# Signal_Conditioner.net
KiCad netlist of a schematic drawn in Altium Designer
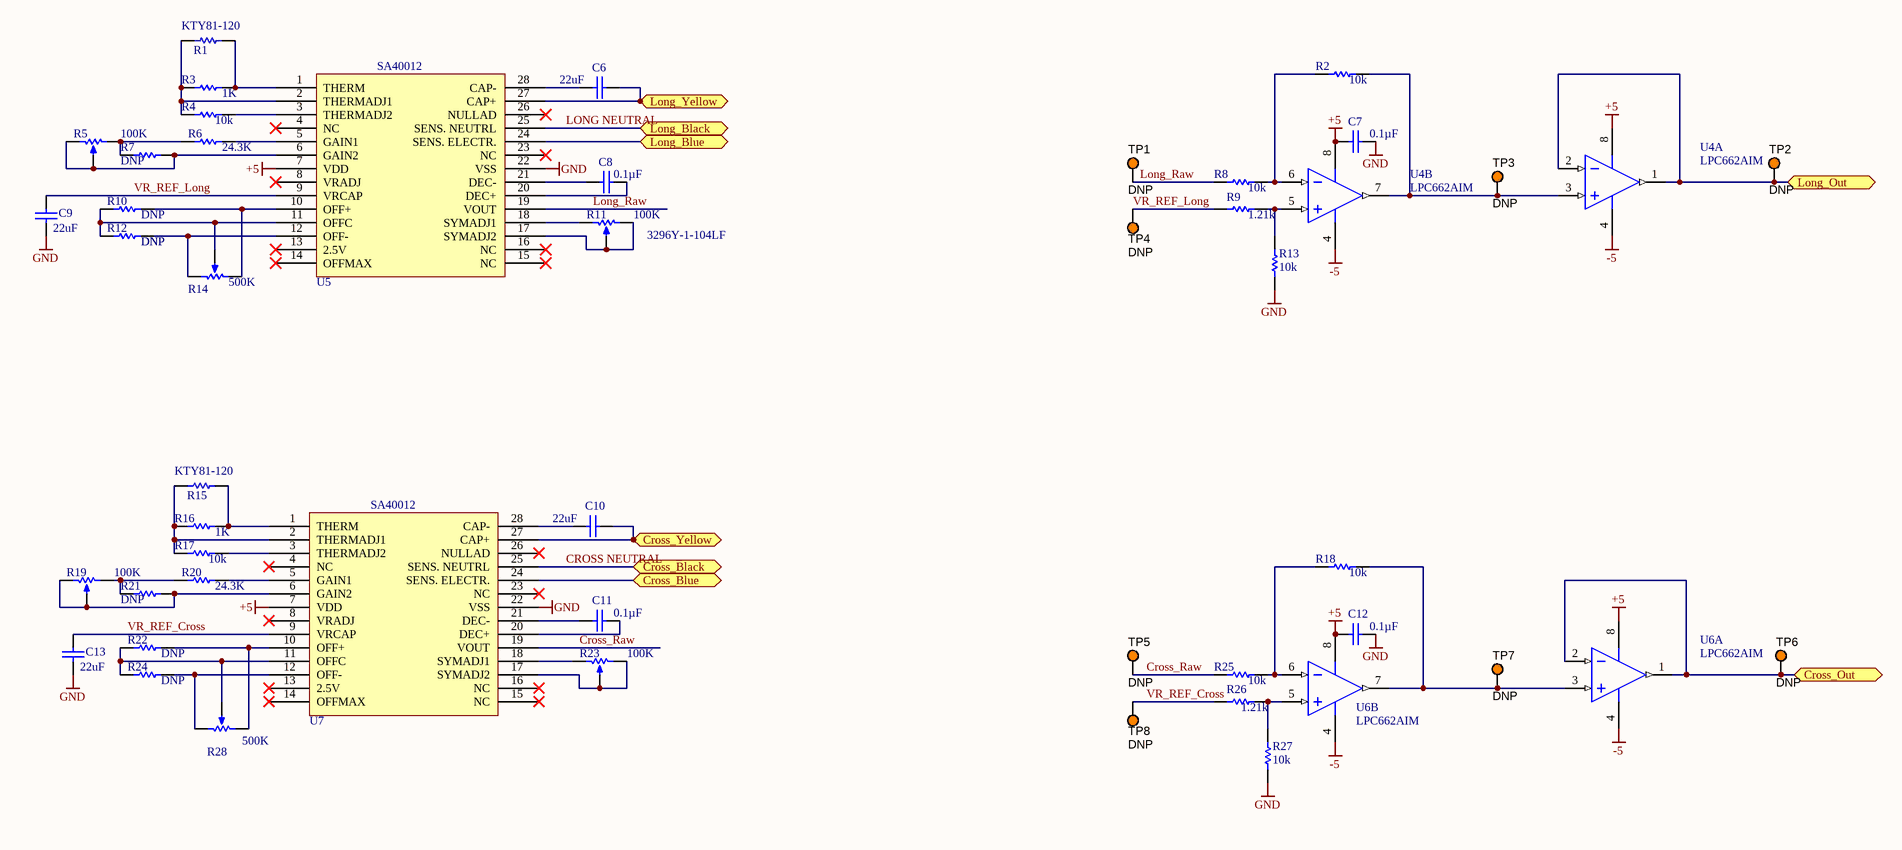
[diagram p0: Signal_Conditioner.SchDoc]

(export (version "E")
  (design (tool "Eeschema 10.0.6"))
  (components
    (comp (ref "C6")
      (value "22uF")
      (footprint "CAPC0805(2012)145_N")
      (description "CAP CER 22UF 16V X5R 0805")
      (fields
        (field (name "MANUFACTURER") "Murata Electronics North America")
        (field (name "MANUFACTURER PART NUMBER") "GRM219R61C226ME15L")
      )
      (libsource (lib "Altium Content Vault") (part "CMP-1036-04795-1"))
    )
    (comp (ref "C7")
      (value "CAP CER 0.1UF 25V X7R 0805")
      (footprint "CAPC0805(2012)145_N")
      (fields
        (field (name "MANUFACTURER") "Murata Electronics North America")
        (field (name "MANUFACTURER PART NUMBER") "GRM21BR71E104KA01L")
        (field (name "CAPACITANCE") "0.1µF")
        (field (name "TOLERANCE") "±10%")
      )
      (libsource (lib "Altium Content Vault") (part "CMP-1036-04795-1"))
    )
    (comp (ref "C8")
      (value "CAP CER 0.1UF 25V X7R 0805")
      (footprint "CAPC0805(2012)145_N")
      (fields
        (field (name "MANUFACTURER") "Murata Electronics North America")
        (field (name "MANUFACTURER PART NUMBER") "GRM21BR71E104KA01L")
        (field (name "CAPACITANCE") "0.1µF")
        (field (name "TOLERANCE") "±10%")
      )
      (libsource (lib "Altium Content Vault") (part "CMP-1036-04795-1"))
    )
    (comp (ref "C9")
      (value "22uF")
      (footprint "CAPC0805(2012)145_N")
      (description "CAP CER 22UF 16V X5R 0805")
      (fields
        (field (name "MANUFACTURER") "Murata Electronics North America")
        (field (name "MANUFACTURER PART NUMBER") "GRM219R61C226ME15L")
      )
      (libsource (lib "Altium Content Vault") (part "CMP-1036-04795-1"))
    )
    (comp (ref "C10")
      (value "22uF")
      (footprint "CAPC0805(2012)145_N")
      (description "CAP CER 22UF 16V X5R 0805")
      (fields
        (field (name "MANUFACTURER") "Murata Electronics North America")
        (field (name "MANUFACTURER PART NUMBER") "GRM219R61C226ME15L")
      )
      (libsource (lib "Altium Content Vault") (part "CMP-1036-04795-1"))
    )
    (comp (ref "C11")
      (value "CAP CER 0.1UF 25V X7R 0805")
      (footprint "CAPC0805(2012)145_N")
      (fields
        (field (name "MANUFACTURER") "Murata Electronics North America")
        (field (name "MANUFACTURER PART NUMBER") "GRM21BR71E104KA01L")
        (field (name "CAPACITANCE") "0.1µF")
        (field (name "TOLERANCE") "±10%")
      )
      (libsource (lib "Altium Content Vault") (part "CMP-1036-04795-1"))
    )
    (comp (ref "C12")
      (value "CAP CER 0.1UF 25V X7R 0805")
      (footprint "CAPC0805(2012)145_N")
      (fields
        (field (name "MANUFACTURER") "Murata Electronics North America")
        (field (name "MANUFACTURER PART NUMBER") "GRM21BR71E104KA01L")
        (field (name "CAPACITANCE") "0.1µF")
        (field (name "TOLERANCE") "±10%")
      )
      (libsource (lib "Altium Content Vault") (part "CMP-1036-04795-1"))
    )
    (comp (ref "C13")
      (value "22uF")
      (footprint "CAPC0805(2012)145_N")
      (description "CAP CER 22UF 16V X5R 0805")
      (fields
        (field (name "MANUFACTURER") "Murata Electronics North America")
        (field (name "MANUFACTURER PART NUMBER") "GRM219R61C226ME15L")
      )
      (libsource (lib "Altium Content Vault") (part "CMP-1036-04795-1"))
    )
    (comp (ref "R1")
      (value "KTY81-120")
      (footprint "KTY81-120")
      (description "THERMISTOR PTC 1K OHM PBCYT2")
      (fields
        (field (name "MANUFACTURER") "NXP USA Inc.")
        (field (name "MANUFACTURER PART NUMBER") "KTY81/120,112")
      )
      (libsource (lib "ZLS_Schematic_lib") (part "KTY81-120"))
    )
    (comp (ref "R2")
      (value "10k")
      (footprint "RESC0805(2012)_L")
      (description "RES SMD 10K OHM 1% 1/8W 0805")
      (fields
        (field (name "MANUFACTURER") "Vishay Dale")
        (field (name "MANUFACTURER PART NUMBER") "CRCW080510K0FKEA")
      )
      (libsource (lib "Altium Content Vault") (part "CMP-1013-00393-1"))
    )
    (comp (ref "R3")
      (value "1K")
      (footprint "RESC0805(2012)_L")
      (description "RES SMD 1K OHM 1% 1/8W 0805")
      (fields
        (field (name "MANUFACTURER") "Vishay Dale")
        (field (name "MANUFACTURER PART NUMBER") "CRCW08051K00FKEA")
      )
      (libsource (lib "Altium Content Vault") (part "CMP-1013-00393-1"))
    )
    (comp (ref "R4")
      (value "10k")
      (footprint "RESC0805(2012)_L")
      (description "RES SMD 10K OHM 1% 1/8W 0805")
      (fields
        (field (name "MANUFACTURER") "Vishay Dale")
        (field (name "MANUFACTURER PART NUMBER") "CRCW080510K0FKEA")
      )
      (libsource (lib "Altium Content Vault") (part "CMP-1013-00393-1"))
    )
    (comp (ref "R5")
      (value "100K")
      (footprint "Trimmer 2.54")
      (description "TRIMMER 5K OHM 0.25W PC PIN")
      (fields
        (field (name "MANUFACTURER") "Bourns Inc.")
        (field (name "MANUFACTURER PART NUMBER") "3296Y-1-104LF")
      )
      (libsource (lib "ZLS_Schematic_lib") (part "Trimmer"))
    )
    (comp (ref "R6")
      (value "24.3K")
      (footprint "RESC0805(2012)_L")
      (description "RES SMD 24.3K OHM 1% 1/8W 0805")
      (fields
        (field (name "MANUFACTURER") "Vishay Dale")
        (field (name "MANUFACTURER PART NUMBER") "CRCW080524K3FKEA")
      )
      (libsource (lib "Altium Content Vault") (part "CMP-1013-00393-1"))
    )
    (comp (ref "R7")
      (value "DNP")
      (footprint "RESC0805(2012)_L")
      (description "RES SMD 10K OHM 1% 1/8W 0805")
      (fields
        (field (name "MANUFACTURER") "Vishay Dale")
        (field (name "MANUFACTURER PART NUMBER") "CRCW080510K0FKEA")
      )
      (libsource (lib "Altium Content Vault") (part "CMP-1013-00393-1"))
    )
    (comp (ref "R8")
      (value "10k")
      (footprint "RESC0805(2012)_L")
      (description "RES SMD 10K OHM 1% 1/8W 0805")
      (fields
        (field (name "MANUFACTURER") "Vishay Dale")
        (field (name "MANUFACTURER PART NUMBER") "CRCW080510K0FKEA")
      )
      (libsource (lib "Altium Content Vault") (part "CMP-1013-00393-1"))
    )
    (comp (ref "R9")
      (value "1.21k")
      (footprint "RESC0805(2012)_L")
      (description "RES SMD 1.21K OHM 1% 1/8W 0805")
      (fields
        (field (name "MANUFACTURER") "Vishay Dale")
        (field (name "MANUFACTURER PART NUMBER") "CRCW08051K21FKEA")
      )
      (libsource (lib "Altium Content Vault") (part "CMP-1013-00393-1"))
    )
    (comp (ref "R10")
      (value "DNP")
      (footprint "RESC0805(2012)_L")
      (description "RES SMD 249K OHM 1% 1/8W 0805")
      (fields
        (field (name "MANUFACTURER") "Vishay Dale")
        (field (name "MANUFACTURER PART NUMBER") "CRCW0805249KFKECC")
      )
      (libsource (lib "Altium Content Vault") (part "CMP-1013-00393-1"))
    )
    (comp (ref "R11")
      (value "100K")
      (footprint "Trimmer 2.54")
      (description "TRIMMER 5K OHM 0.25W PC PIN")
      (fields
        (field (name "MANUFACTURER") "Bourns Inc.")
        (field (name "MANUFACTURER PART NUMBER") "3296Y-1-104LF")
      )
      (libsource (lib "ZLS_Schematic_lib") (part "Trimmer"))
    )
    (comp (ref "R12")
      (value "DNP")
      (footprint "RESC0805(2012)_L")
      (description "RES SMD 249K OHM 1% 1/8W 0805")
      (fields
        (field (name "MANUFACTURER") "Vishay Dale")
        (field (name "MANUFACTURER PART NUMBER") "CRCW0805249KFKECC")
      )
      (libsource (lib "Altium Content Vault") (part "CMP-1013-00393-1"))
    )
    (comp (ref "R13")
      (value "10k")
      (footprint "RESC0805(2012)_L")
      (description "RES SMD 10K OHM 1% 1/8W 0805")
      (fields
        (field (name "MANUFACTURER") "Vishay Dale")
        (field (name "MANUFACTURER PART NUMBER") "CRCW080510K0FKEA")
      )
      (libsource (lib "Altium Content Vault") (part "CMP-1013-00393-1"))
    )
    (comp (ref "R14")
      (value "500K")
      (footprint "Trimmer 2.54")
      (description "TRIMMER 500K OHM 0.5W PC PIN TOP")
      (fields
        (field (name "MANUFACTURER") "Bourns Inc.")
        (field (name "MANUFACTURER PART NUMBER") "3296Y-1-504LF")
      )
      (libsource (lib "ZLS_Schematic_lib") (part "Trimmer"))
    )
    (comp (ref "R15")
      (value "KTY81-120")
      (footprint "KTY81-120")
      (description "THERMISTOR PTC 1K OHM PBCYT2")
      (fields
        (field (name "MANUFACTURER") "NXP USA Inc.")
        (field (name "MANUFACTURER PART NUMBER") "KTY81/120,112")
      )
      (libsource (lib "ZLS_Schematic_lib") (part "KTY81-120"))
    )
    (comp (ref "R16")
      (value "1K")
      (footprint "RESC0805(2012)_L")
      (description "RES SMD 1K OHM 1% 1/8W 0805")
      (fields
        (field (name "MANUFACTURER") "Vishay Dale")
        (field (name "MANUFACTURER PART NUMBER") "CRCW08051K00FKEA")
      )
      (libsource (lib "Altium Content Vault") (part "CMP-1013-00393-1"))
    )
    (comp (ref "R17")
      (value "10k")
      (footprint "RESC0805(2012)_L")
      (description "RES SMD 10K OHM 1% 1/8W 0805")
      (fields
        (field (name "MANUFACTURER") "Vishay Dale")
        (field (name "MANUFACTURER PART NUMBER") "CRCW080510K0FKEA")
      )
      (libsource (lib "Altium Content Vault") (part "CMP-1013-00393-1"))
    )
    (comp (ref "R18")
      (value "10k")
      (footprint "RESC0805(2012)_L")
      (description "RES SMD 10K OHM 1% 1/8W 0805")
      (fields
        (field (name "MANUFACTURER") "Vishay Dale")
        (field (name "MANUFACTURER PART NUMBER") "CRCW080510K0FKEA")
      )
      (libsource (lib "Altium Content Vault") (part "CMP-1013-00393-1"))
    )
    (comp (ref "R19")
      (value "100K")
      (footprint "Trimmer 2.54")
      (description "TRIMMER 5K OHM 0.25W PC PIN")
      (fields
        (field (name "MANUFACTURER") "Bourns Inc.")
        (field (name "MANUFACTURER PART NUMBER") "3296Y-1-104LF")
      )
      (libsource (lib "ZLS_Schematic_lib") (part "Trimmer"))
    )
    (comp (ref "R20")
      (value "24.3K")
      (footprint "RESC0805(2012)_L")
      (description "RES SMD 24.3K OHM 1% 1/8W 0805")
      (fields
        (field (name "MANUFACTURER") "Vishay Dale")
        (field (name "MANUFACTURER PART NUMBER") "CRCW080524K3FKEA")
      )
      (libsource (lib "Altium Content Vault") (part "CMP-1013-00393-1"))
    )
    (comp (ref "R21")
      (value "DNP")
      (footprint "RESC0805(2012)_L")
      (description "RES SMD 10K OHM 1% 1/8W 0805")
      (fields
        (field (name "MANUFACTURER") "Vishay Dale")
        (field (name "MANUFACTURER PART NUMBER") "CRCW080510K0FKEA")
      )
      (libsource (lib "Altium Content Vault") (part "CMP-1013-00393-1"))
    )
    (comp (ref "R22")
      (value "DNP")
      (footprint "RESC0805(2012)_L")
      (description "RES SMD 249K OHM 1% 1/8W 0805")
      (fields
        (field (name "MANUFACTURER") "Vishay Dale")
        (field (name "MANUFACTURER PART NUMBER") "CRCW0805249KFKECC")
      )
      (libsource (lib "Altium Content Vault") (part "CMP-1013-00393-1"))
    )
    (comp (ref "R23")
      (value "100K")
      (footprint "Trimmer 2.54")
      (description "TRIMMER 5K OHM 0.25W PC PIN")
      (fields
        (field (name "MANUFACTURER") "Bourns Inc.")
        (field (name "MANUFACTURER PART NUMBER") "3296Y-1-104LF")
      )
      (libsource (lib "ZLS_Schematic_lib") (part "Trimmer"))
    )
    (comp (ref "R24")
      (value "DNP")
      (footprint "RESC0805(2012)_L")
      (description "RES SMD 249K OHM 1% 1/8W 0805")
      (fields
        (field (name "MANUFACTURER") "Vishay Dale")
        (field (name "MANUFACTURER PART NUMBER") "CRCW0805249KFKECC")
      )
      (libsource (lib "Altium Content Vault") (part "CMP-1013-00393-1"))
    )
    (comp (ref "R25")
      (value "10k")
      (footprint "RESC0805(2012)_L")
      (description "RES SMD 10K OHM 1% 1/8W 0805")
      (fields
        (field (name "MANUFACTURER") "Vishay Dale")
        (field (name "MANUFACTURER PART NUMBER") "CRCW080510K0FKEA")
      )
      (libsource (lib "Altium Content Vault") (part "CMP-1013-00393-1"))
    )
    (comp (ref "R26")
      (value "1.21k")
      (footprint "RESC0805(2012)_L")
      (description "RES SMD 1.21K OHM 1% 1/8W 0805")
      (fields
        (field (name "MANUFACTURER") "Vishay Dale")
        (field (name "MANUFACTURER PART NUMBER") "CRCW08051K21FKEA")
      )
      (libsource (lib "Altium Content Vault") (part "CMP-1013-00393-1"))
    )
    (comp (ref "R27")
      (value "10k")
      (footprint "RESC0805(2012)_L")
      (description "RES SMD 10K OHM 1% 1/8W 0805")
      (fields
        (field (name "MANUFACTURER") "Vishay Dale")
        (field (name "MANUFACTURER PART NUMBER") "CRCW080510K0FKEA")
      )
      (libsource (lib "Altium Content Vault") (part "CMP-1013-00393-1"))
    )
    (comp (ref "R28")
      (value "500K")
      (footprint "Trimmer 2.54")
      (description "TRIMMER 500K OHM 0.5W PC PIN TOP")
      (fields
        (field (name "MANUFACTURER") "Bourns Inc.")
        (field (name "MANUFACTURER PART NUMBER") "3296Y-1-504LF")
      )
      (libsource (lib "ZLS_Schematic_lib") (part "Trimmer"))
    )
    (comp (ref "TP1")
      (value "DNP")
      (footprint "KSTN-5003")
      (description "Test Point, Orange, 1-Pin THD, RoHS")
      (fields
        (field (name "MANUFACTURER") "Keystone Electronics")
        (field (name "MANUFACTURER PART NUMBER") "5003")
      )
      (libsource (lib "Altium Content Vault") (part "CMP-1672-00009-1"))
    )
    (comp (ref "TP2")
      (value "DNP")
      (footprint "KSTN-5003")
      (description "Test Point, Orange, 1-Pin THD, RoHS")
      (fields
        (field (name "MANUFACTURER") "Keystone Electronics")
        (field (name "MANUFACTURER PART NUMBER") "5003")
      )
      (libsource (lib "Altium Content Vault") (part "CMP-1672-00009-1"))
    )
    (comp (ref "TP3")
      (value "DNP")
      (footprint "KSTN-5003")
      (description "Test Point, Orange, 1-Pin THD, RoHS")
      (fields
        (field (name "MANUFACTURER") "Keystone Electronics")
        (field (name "MANUFACTURER PART NUMBER") "5003")
      )
      (libsource (lib "Altium Content Vault") (part "CMP-1672-00009-1"))
    )
    (comp (ref "TP4")
      (value "DNP")
      (footprint "KSTN-5003")
      (description "Test Point, Orange, 1-Pin THD, RoHS")
      (fields
        (field (name "MANUFACTURER") "Keystone Electronics")
        (field (name "MANUFACTURER PART NUMBER") "5003")
      )
      (libsource (lib "Altium Content Vault") (part "CMP-1672-00009-1"))
    )
    (comp (ref "TP5")
      (value "DNP")
      (footprint "KSTN-5003")
      (description "Test Point, Orange, 1-Pin THD, RoHS")
      (fields
        (field (name "MANUFACTURER") "Keystone Electronics")
        (field (name "MANUFACTURER PART NUMBER") "5003")
      )
      (libsource (lib "Altium Content Vault") (part "CMP-1672-00009-1"))
    )
    (comp (ref "TP6")
      (value "DNP")
      (footprint "KSTN-5003")
      (description "Test Point, Orange, 1-Pin THD, RoHS")
      (fields
        (field (name "MANUFACTURER") "Keystone Electronics")
        (field (name "MANUFACTURER PART NUMBER") "5003")
      )
      (libsource (lib "Altium Content Vault") (part "CMP-1672-00009-1"))
    )
    (comp (ref "TP7")
      (value "DNP")
      (footprint "KSTN-5003")
      (description "Test Point, Orange, 1-Pin THD, RoHS")
      (fields
        (field (name "MANUFACTURER") "Keystone Electronics")
        (field (name "MANUFACTURER PART NUMBER") "5003")
      )
      (libsource (lib "Altium Content Vault") (part "CMP-1672-00009-1"))
    )
    (comp (ref "TP8")
      (value "DNP")
      (footprint "KSTN-5003")
      (description "Test Point, Orange, 1-Pin THD, RoHS")
      (fields
        (field (name "MANUFACTURER") "Keystone Electronics")
        (field (name "MANUFACTURER PART NUMBER") "5003")
      )
      (libsource (lib "Altium Content Vault") (part "CMP-1672-00009-1"))
    )
    (comp (ref "U4")
      (value "LPC662AIM")
      (footprint "D0008A_M")
      (description "Low Power CMOS Dual Operational Amplifier, 8-pin Narrow SOIC")
      (fields (field (name "MANUFACTURER") "Texas Instruments"))
      (libsource (lib "Altium Content Vault") (part "AMP-OPA-LM6132-8"))
    )
    (comp (ref "U5")
      (value "SA40012")
      (footprint "SA40012")
      (description "Single Axix CMOS Signal Conditioning Module")
      (fields (field (name "MANUFACTURER") "Spectron") (field (name "MANUFACTURER PART NUMBER") "A40012"))
      (libsource (lib "ZLS_Schematic_lib") (part "SA40012"))
    )
    (comp (ref "U6")
      (value "LPC662AIM")
      (footprint "D0008A_M")
      (description "Low Power CMOS Dual Operational Amplifier, 8-pin Narrow SOIC")
      (fields
        (field (name "MANUFACTURER") "Texas Instruments")
        (field (name "MANUFACTURER PART NUMBER") "LPC662AIMX/NOPB")
      )
      (libsource (lib "Altium Content Vault") (part "CMP-0055-00867-3"))
    )
    (comp (ref "U7")
      (value "SA40012")
      (footprint "SA40012")
      (description "Single Axix CMOS Signal Conditioning Module")
      (fields (field (name "MANUFACTURER") "Spectron") (field (name "MANUFACTURER PART NUMBER") "A40012"))
      (libsource (lib "ZLS_Schematic_lib") (part "SA40012"))
    )
  )
  (nets
    (net (code "1") (name "+5") (class "Default")
      (node (ref "C12") (pin "1") (pinfunction "1_1") (pintype "passive"))
      (node (ref "C7") (pin "1") (pinfunction "1_1") (pintype "passive"))
      (node (ref "U4") (pin "8") (pinfunction "V+_8") (pintype "power_in"))
      (node (ref "U5") (pin "7") (pinfunction "VDD_7") (pintype "passive"))
      (node (ref "U6") (pin "8") (pinfunction "V+_8") (pintype "power_in"))
      (node (ref "U7") (pin "7") (pinfunction "VDD_7") (pintype "passive"))
    )
    (net (code "2") (name "-5") (class "Default")
      (node (ref "U4") (pin "4") (pinfunction "V-_4") (pintype "power_in"))
      (node (ref "U6") (pin "4") (pinfunction "V-_4") (pintype "power_in"))
    )
    (net (code "3") (name "/CROSS NEUTRAL") (class "Default")
      (node (ref "U7") (pin "25") (pinfunction "SENS._NEUTRL_25") (pintype "passive"))
    )
    (net (code "4") (name "/Cross_Blue") (class "Default")
      (node (ref "U7") (pin "24") (pinfunction "SENS._ELECTR._24") (pintype "passive"))
    )
    (net (code "5") (name "/Cross_Out") (class "Default")
      (node (ref "TP6") (pin "1") (pinfunction "1_1") (pintype "passive"))
      (node (ref "U6") (pin "1") (pinfunction "OUTA_1") (pintype "output"))
      (node (ref "U6") (pin "2") (pinfunction "INA-_2") (pintype "input"))
    )
    (net (code "6") (name "/Cross_Raw") (class "Default")
      (node (ref "R25") (pin "1") (pinfunction "1_1") (pintype "passive"))
      (node (ref "TP5") (pin "1") (pinfunction "1_1") (pintype "passive"))
      (node (ref "U7") (pin "19") (pinfunction "VOUT_19") (pintype "passive"))
    )
    (net (code "7") (name "/Cross_Yellow") (class "Default")
      (node (ref "C10") (pin "2") (pinfunction "2_2") (pintype "passive"))
      (node (ref "U7") (pin "27") (pinfunction "CAP+_27") (pintype "passive"))
    )
    (net (code "8") (name "/LONG NEUTRAL") (class "Default")
      (node (ref "U5") (pin "25") (pinfunction "SENS._NEUTRL_25") (pintype "passive"))
    )
    (net (code "9") (name "/Long_Blue") (class "Default")
      (node (ref "U5") (pin "24") (pinfunction "SENS._ELECTR._24") (pintype "passive"))
    )
    (net (code "10") (name "/Long_Out") (class "Default")
      (node (ref "TP2") (pin "1") (pinfunction "1_1") (pintype "passive"))
      (node (ref "U4") (pin "1") (pinfunction "OUTA_1") (pintype "output"))
      (node (ref "U4") (pin "2") (pinfunction "INA-_2") (pintype "input"))
    )
    (net (code "11") (name "/Long_Raw") (class "Default")
      (node (ref "R8") (pin "1") (pinfunction "1_1") (pintype "passive"))
      (node (ref "TP1") (pin "1") (pinfunction "1_1") (pintype "passive"))
      (node (ref "U5") (pin "19") (pinfunction "VOUT_19") (pintype "passive"))
    )
    (net (code "12") (name "/Long_Yellow") (class "Default")
      (node (ref "C6") (pin "2") (pinfunction "2_2") (pintype "passive"))
      (node (ref "U5") (pin "27") (pinfunction "CAP+_27") (pintype "passive"))
    )
    (net (code "13") (name "/VR_REF_Cross") (class "Default")
      (node (ref "C13") (pin "1") (pinfunction "1_1") (pintype "passive"))
      (node (ref "R26") (pin "2") (pinfunction "2_2") (pintype "passive"))
      (node (ref "TP8") (pin "1") (pinfunction "1_1") (pintype "passive"))
      (node (ref "U7") (pin "9") (pinfunction "VRCAP_9") (pintype "passive"))
    )
    (net (code "14") (name "/VR_REF_Long") (class "Default")
      (node (ref "C9") (pin "1") (pinfunction "1_1") (pintype "passive"))
      (node (ref "R9") (pin "2") (pinfunction "2_2") (pintype "passive"))
      (node (ref "TP4") (pin "1") (pinfunction "1_1") (pintype "passive"))
      (node (ref "U5") (pin "9") (pinfunction "VRCAP_9") (pintype "passive"))
    )
    (net (code "15") (name "GND") (class "Default")
      (node (ref "C12") (pin "2") (pinfunction "2_2") (pintype "passive"))
      (node (ref "C13") (pin "2") (pinfunction "2_2") (pintype "passive"))
      (node (ref "C7") (pin "2") (pinfunction "2_2") (pintype "passive"))
      (node (ref "C9") (pin "2") (pinfunction "2_2") (pintype "passive"))
      (node (ref "R13") (pin "1") (pinfunction "1_1") (pintype "passive"))
      (node (ref "R27") (pin "1") (pinfunction "1_1") (pintype "passive"))
      (node (ref "U5") (pin "22") (pinfunction "VSS_22") (pintype "passive"))
      (node (ref "U7") (pin "22") (pinfunction "VSS_22") (pintype "passive"))
    )
    (net (code "16") (name "Net-(R5-a)") (class "Default")
      (node (ref "R5") (pin "1") (pinfunction "a_1") (pintype "passive"))
      (node (ref "R5") (pin "2") (pinfunction "b_2") (pintype "passive"))
      (node (ref "R7") (pin "2") (pinfunction "2_2") (pintype "passive"))
      (node (ref "U5") (pin "6") (pinfunction "GAIN2_6") (pintype "passive"))
    )
    (net (code "17") (name "Net-(R5-c)") (class "Default")
      (node (ref "R5") (pin "3") (pinfunction "c_3") (pintype "passive"))
      (node (ref "R6") (pin "1") (pinfunction "1_1") (pintype "passive"))
      (node (ref "R7") (pin "1") (pinfunction "1_1") (pintype "passive"))
    )
    (net (code "18") (name "Net-(R11-a)") (class "Default")
      (node (ref "R11") (pin "1") (pinfunction "a_1") (pintype "passive"))
      (node (ref "U5") (pin "18") (pinfunction "SYMADJ1_18") (pintype "passive"))
    )
    (net (code "19") (name "Net-(R11-b)") (class "Default")
      (node (ref "R11") (pin "2") (pinfunction "b_2") (pintype "passive"))
      (node (ref "R11") (pin "3") (pinfunction "c_3") (pintype "passive"))
      (node (ref "U5") (pin "17") (pinfunction "SYMADJ2_17") (pintype "passive"))
    )
    (net (code "20") (name "Net-(R14-a)") (class "Default")
      (node (ref "R10") (pin "2") (pinfunction "2_2") (pintype "passive"))
      (node (ref "R14") (pin "1") (pinfunction "a_1") (pintype "passive"))
      (node (ref "U5") (pin "10") (pinfunction "OFF+_10") (pintype "passive"))
    )
    (net (code "21") (name "Net-(R14-b)") (class "Default")
      (node (ref "R10") (pin "1") (pinfunction "1_1") (pintype "passive"))
      (node (ref "R12") (pin "1") (pinfunction "1_1") (pintype "passive"))
      (node (ref "R14") (pin "2") (pinfunction "b_2") (pintype "passive"))
      (node (ref "U5") (pin "11") (pinfunction "OFFC_11") (pintype "passive"))
    )
    (net (code "22") (name "Net-(R14-c)") (class "Default")
      (node (ref "R12") (pin "2") (pinfunction "2_2") (pintype "passive"))
      (node (ref "R14") (pin "3") (pinfunction "c_3") (pintype "passive"))
      (node (ref "U5") (pin "12") (pinfunction "OFF-_12") (pintype "passive"))
    )
    (net (code "23") (name "Net-(R19-a)") (class "Default")
      (node (ref "R19") (pin "1") (pinfunction "a_1") (pintype "passive"))
      (node (ref "R19") (pin "2") (pinfunction "b_2") (pintype "passive"))
      (node (ref "R21") (pin "2") (pinfunction "2_2") (pintype "passive"))
      (node (ref "U7") (pin "6") (pinfunction "GAIN2_6") (pintype "passive"))
    )
    (net (code "24") (name "Net-(R19-c)") (class "Default")
      (node (ref "R19") (pin "3") (pinfunction "c_3") (pintype "passive"))
      (node (ref "R20") (pin "1") (pinfunction "1_1") (pintype "passive"))
      (node (ref "R21") (pin "1") (pinfunction "1_1") (pintype "passive"))
    )
    (net (code "25") (name "Net-(R23-a)") (class "Default")
      (node (ref "R23") (pin "1") (pinfunction "a_1") (pintype "passive"))
      (node (ref "U7") (pin "18") (pinfunction "SYMADJ1_18") (pintype "passive"))
    )
    (net (code "26") (name "Net-(R23-b)") (class "Default")
      (node (ref "R23") (pin "2") (pinfunction "b_2") (pintype "passive"))
      (node (ref "R23") (pin "3") (pinfunction "c_3") (pintype "passive"))
      (node (ref "U7") (pin "17") (pinfunction "SYMADJ2_17") (pintype "passive"))
    )
    (net (code "27") (name "Net-(R28-a)") (class "Default")
      (node (ref "R22") (pin "2") (pinfunction "2_2") (pintype "passive"))
      (node (ref "R28") (pin "1") (pinfunction "a_1") (pintype "passive"))
      (node (ref "U7") (pin "10") (pinfunction "OFF+_10") (pintype "passive"))
    )
    (net (code "28") (name "Net-(R28-b)") (class "Default")
      (node (ref "R22") (pin "1") (pinfunction "1_1") (pintype "passive"))
      (node (ref "R24") (pin "1") (pinfunction "1_1") (pintype "passive"))
      (node (ref "R28") (pin "2") (pinfunction "b_2") (pintype "passive"))
      (node (ref "U7") (pin "11") (pinfunction "OFFC_11") (pintype "passive"))
    )
    (net (code "29") (name "Net-(R28-c)") (class "Default")
      (node (ref "R24") (pin "2") (pinfunction "2_2") (pintype "passive"))
      (node (ref "R28") (pin "3") (pinfunction "c_3") (pintype "passive"))
      (node (ref "U7") (pin "12") (pinfunction "OFF-_12") (pintype "passive"))
    )
    (net (code "30") (name "Net-(U4A-INA+)") (class "Default")
      (node (ref "R2") (pin "2") (pinfunction "2_2") (pintype "passive"))
      (node (ref "TP3") (pin "1") (pinfunction "1_1") (pintype "passive"))
      (node (ref "U4") (pin "3") (pinfunction "INA+_3") (pintype "input"))
      (node (ref "U4") (pin "7") (pinfunction "OUTB_7") (pintype "output"))
    )
    (net (code "31") (name "Net-(U4B-INB+)") (class "Default")
      (node (ref "R13") (pin "2") (pinfunction "2_2") (pintype "passive"))
      (node (ref "R9") (pin "1") (pinfunction "1_1") (pintype "passive"))
      (node (ref "U4") (pin "5") (pinfunction "INB+_5") (pintype "input"))
    )
    (net (code "32") (name "Net-(U4B-INB-)") (class "Default")
      (node (ref "R2") (pin "1") (pinfunction "1_1") (pintype "passive"))
      (node (ref "R8") (pin "2") (pinfunction "2_2") (pintype "passive"))
      (node (ref "U4") (pin "6") (pinfunction "INB-_6") (pintype "input"))
    )
    (net (code "33") (name "Net-(U5-CAP-)") (class "Default")
      (node (ref "C6") (pin "1") (pinfunction "1_1") (pintype "passive"))
      (node (ref "U5") (pin "28") (pinfunction "CAP-_28") (pintype "passive"))
    )
    (net (code "34") (name "Net-(U5-DEC+)") (class "Default")
      (node (ref "C8") (pin "2") (pinfunction "2_2") (pintype "passive"))
      (node (ref "U5") (pin "20") (pinfunction "DEC+_20") (pintype "passive"))
    )
    (net (code "35") (name "Net-(U5-DEC-)") (class "Default")
      (node (ref "C8") (pin "1") (pinfunction "1_1") (pintype "passive"))
      (node (ref "U5") (pin "21") (pinfunction "DEC-_21") (pintype "passive"))
    )
    (net (code "36") (name "Net-(U5-GAIN1)") (class "Default")
      (node (ref "R6") (pin "2") (pinfunction "2_2") (pintype "passive"))
      (node (ref "U5") (pin "5") (pinfunction "GAIN1_5") (pintype "passive"))
    )
    (net (code "37") (name "Net-(U5-THERM)") (class "Default")
      (node (ref "R1") (pin "2") (pinfunction "2_2") (pintype "passive"))
      (node (ref "R3") (pin "2") (pinfunction "2_2") (pintype "passive"))
      (node (ref "U5") (pin "1") (pinfunction "THERM_1") (pintype "passive"))
    )
    (net (code "38") (name "Net-(U5-THERMADJ1)") (class "Default")
      (node (ref "R1") (pin "1") (pinfunction "1_1") (pintype "passive"))
      (node (ref "R3") (pin "1") (pinfunction "1_1") (pintype "passive"))
      (node (ref "R4") (pin "1") (pinfunction "1_1") (pintype "passive"))
      (node (ref "U5") (pin "2") (pinfunction "THERMADJ1_2") (pintype "passive"))
    )
    (net (code "39") (name "Net-(U5-THERMADJ2)") (class "Default")
      (node (ref "R4") (pin "2") (pinfunction "2_2") (pintype "passive"))
      (node (ref "U5") (pin "3") (pinfunction "THERMADJ2_3") (pintype "passive"))
    )
    (net (code "40") (name "Net-(U6A-INA+)") (class "Default")
      (node (ref "R18") (pin "2") (pinfunction "2_2") (pintype "passive"))
      (node (ref "TP7") (pin "1") (pinfunction "1_1") (pintype "passive"))
      (node (ref "U6") (pin "3") (pinfunction "INA+_3") (pintype "input"))
      (node (ref "U6") (pin "7") (pinfunction "OUTB_7") (pintype "output"))
    )
    (net (code "41") (name "Net-(U6B-INB+)") (class "Default")
      (node (ref "R26") (pin "1") (pinfunction "1_1") (pintype "passive"))
      (node (ref "R27") (pin "2") (pinfunction "2_2") (pintype "passive"))
      (node (ref "U6") (pin "5") (pinfunction "INB+_5") (pintype "input"))
    )
    (net (code "42") (name "Net-(U6B-INB-)") (class "Default")
      (node (ref "R18") (pin "1") (pinfunction "1_1") (pintype "passive"))
      (node (ref "R25") (pin "2") (pinfunction "2_2") (pintype "passive"))
      (node (ref "U6") (pin "6") (pinfunction "INB-_6") (pintype "input"))
    )
    (net (code "43") (name "Net-(U7-CAP-)") (class "Default")
      (node (ref "C10") (pin "1") (pinfunction "1_1") (pintype "passive"))
      (node (ref "U7") (pin "28") (pinfunction "CAP-_28") (pintype "passive"))
    )
    (net (code "44") (name "Net-(U7-DEC+)") (class "Default")
      (node (ref "C11") (pin "2") (pinfunction "2_2") (pintype "passive"))
      (node (ref "U7") (pin "20") (pinfunction "DEC+_20") (pintype "passive"))
    )
    (net (code "45") (name "Net-(U7-DEC-)") (class "Default")
      (node (ref "C11") (pin "1") (pinfunction "1_1") (pintype "passive"))
      (node (ref "U7") (pin "21") (pinfunction "DEC-_21") (pintype "passive"))
    )
    (net (code "46") (name "Net-(U7-GAIN1)") (class "Default")
      (node (ref "R20") (pin "2") (pinfunction "2_2") (pintype "passive"))
      (node (ref "U7") (pin "5") (pinfunction "GAIN1_5") (pintype "passive"))
    )
    (net (code "47") (name "Net-(U7-THERM)") (class "Default")
      (node (ref "R15") (pin "2") (pinfunction "2_2") (pintype "passive"))
      (node (ref "R16") (pin "2") (pinfunction "2_2") (pintype "passive"))
      (node (ref "U7") (pin "1") (pinfunction "THERM_1") (pintype "passive"))
    )
    (net (code "48") (name "Net-(U7-THERMADJ1)") (class "Default")
      (node (ref "R15") (pin "1") (pinfunction "1_1") (pintype "passive"))
      (node (ref "R16") (pin "1") (pinfunction "1_1") (pintype "passive"))
      (node (ref "R17") (pin "1") (pinfunction "1_1") (pintype "passive"))
      (node (ref "U7") (pin "2") (pinfunction "THERMADJ1_2") (pintype "passive"))
    )
    (net (code "49") (name "Net-(U7-THERMADJ2)") (class "Default")
      (node (ref "R17") (pin "2") (pinfunction "2_2") (pintype "passive"))
      (node (ref "U7") (pin "3") (pinfunction "THERMADJ2_3") (pintype "passive"))
    )
    (net (code "50") (name "unconnected-(U5-2.5V-Pad13)") (class "Default")
      (node (ref "U5") (pin "13") (pinfunction "2.5V_13") (pintype "passive+no_connect"))
    )
    (net (code "51") (name "unconnected-(U5-NC-Pad4)") (class "Default")
      (node (ref "U5") (pin "4") (pinfunction "NC_4") (pintype "passive+no_connect"))
    )
    (net (code "52") (name "unconnected-(U5-NC-Pad15)") (class "Default")
      (node (ref "U5") (pin "15") (pinfunction "NC_15") (pintype "passive+no_connect"))
    )
    (net (code "53") (name "unconnected-(U5-NC-Pad16)") (class "Default")
      (node (ref "U5") (pin "16") (pinfunction "NC_16") (pintype "passive+no_connect"))
    )
    (net (code "54") (name "unconnected-(U5-NC-Pad23)") (class "Default")
      (node (ref "U5") (pin "23") (pinfunction "NC_23") (pintype "passive+no_connect"))
    )
    (net (code "55") (name "unconnected-(U5-NULLAD-Pad26)") (class "Default")
      (node (ref "U5") (pin "26") (pinfunction "NULLAD_26") (pintype "passive+no_connect"))
    )
    (net (code "56") (name "unconnected-(U5-OFFMAX-Pad14)") (class "Default")
      (node (ref "U5") (pin "14") (pinfunction "OFFMAX_14") (pintype "passive+no_connect"))
    )
    (net (code "57") (name "unconnected-(U5-VRADJ-Pad8)") (class "Default")
      (node (ref "U5") (pin "8") (pinfunction "VRADJ_8") (pintype "passive+no_connect"))
    )
    (net (code "58") (name "unconnected-(U7-2.5V-Pad13)") (class "Default")
      (node (ref "U7") (pin "13") (pinfunction "2.5V_13") (pintype "passive+no_connect"))
    )
    (net (code "59") (name "unconnected-(U7-NC-Pad4)") (class "Default")
      (node (ref "U7") (pin "4") (pinfunction "NC_4") (pintype "passive+no_connect"))
    )
    (net (code "60") (name "unconnected-(U7-NC-Pad15)") (class "Default")
      (node (ref "U7") (pin "15") (pinfunction "NC_15") (pintype "passive+no_connect"))
    )
    (net (code "61") (name "unconnected-(U7-NC-Pad16)") (class "Default")
      (node (ref "U7") (pin "16") (pinfunction "NC_16") (pintype "passive+no_connect"))
    )
    (net (code "62") (name "unconnected-(U7-NC-Pad23)") (class "Default")
      (node (ref "U7") (pin "23") (pinfunction "NC_23") (pintype "passive+no_connect"))
    )
    (net (code "63") (name "unconnected-(U7-NULLAD-Pad26)") (class "Default")
      (node (ref "U7") (pin "26") (pinfunction "NULLAD_26") (pintype "passive+no_connect"))
    )
    (net (code "64") (name "unconnected-(U7-OFFMAX-Pad14)") (class "Default")
      (node (ref "U7") (pin "14") (pinfunction "OFFMAX_14") (pintype "passive+no_connect"))
    )
    (net (code "65") (name "unconnected-(U7-VRADJ-Pad8)") (class "Default")
      (node (ref "U7") (pin "8") (pinfunction "VRADJ_8") (pintype "passive+no_connect"))
    )
  )
)
